# M_dulo_U_V_v_1_0.net
KiCad netlist of a schematic drawn in EAGLE
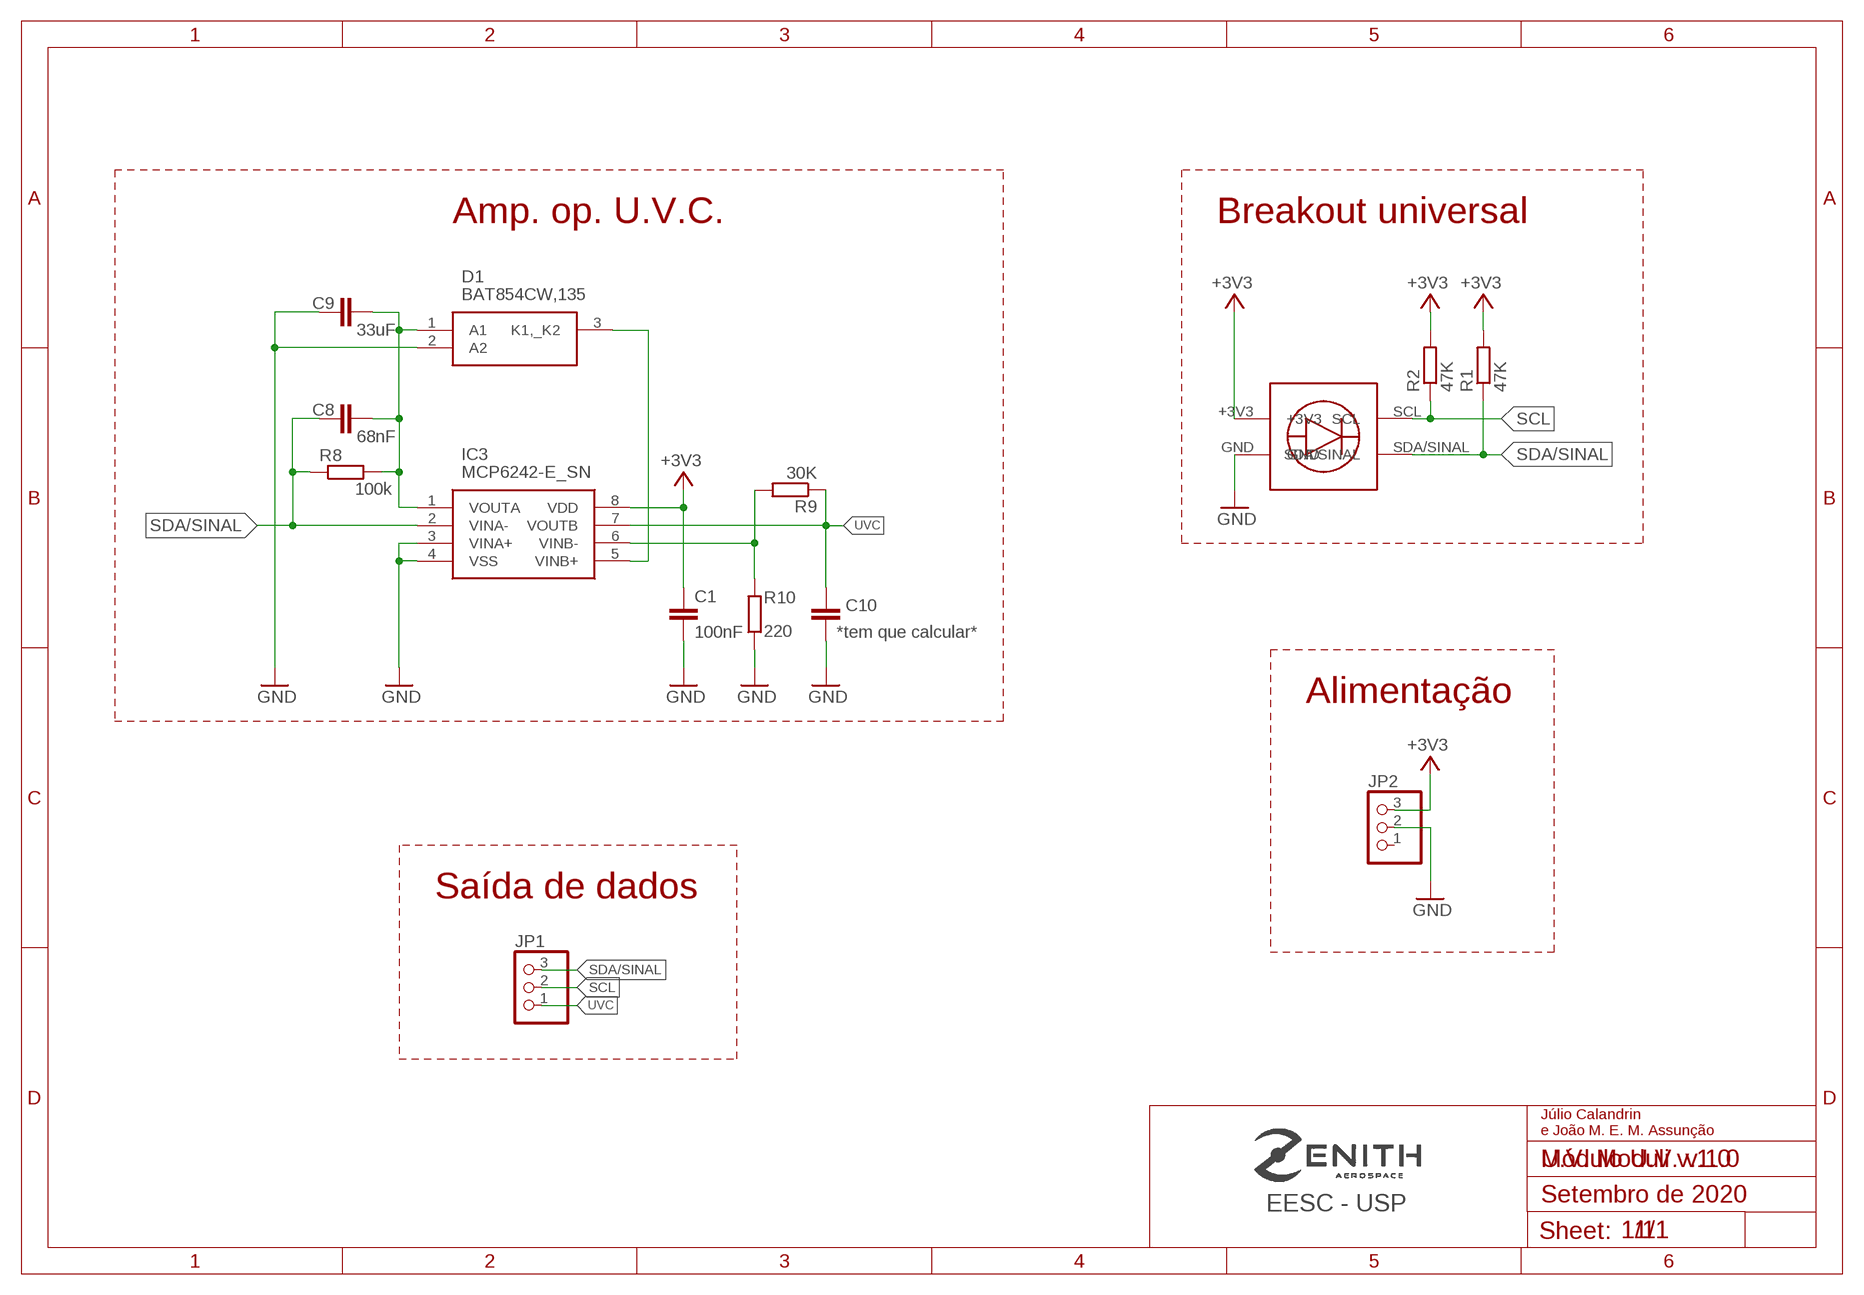
[diagram p0: schematic, sheet 1]

(export (version "E")
  (design (tool "Eeschema 10.0.6"))
  (components
    (comp (ref "C1")
      (value "100nF")
      (footprint "eagle-import:C0805")
      (libsource (lib "eagle-import") (part "C-EUC0805"))
    )
    (comp (ref "C8")
      (value "68nF")
      (footprint "eagle-import:C0805")
      (libsource (lib "eagle-import") (part "C-EUC0805"))
    )
    (comp (ref "C9")
      (value "33uF")
      (footprint "eagle-import:C0805")
      (libsource (lib "eagle-import") (part "C-EUC0805"))
    )
    (comp (ref "C10")
      (value "*tem que calcular*")
      (footprint "eagle-import:C0805")
      (libsource (lib "eagle-import") (part "C-EUC0805"))
    )
    (comp (ref "D1")
      (value "BAT854CW,135")
      (footprint "eagle-import:SOT65P210X110-3N")
      (fields (field (name "MOUSER_PART_NUMBER") "771-BAT854CW,135"))
      (libsource (lib "eagle-import") (part "BAT854CW,135"))
    )
    (comp (ref "IC3")
      (value "MCP6242-E_SN")
      (footprint "eagle-import:SOIC127P600X175-8N")
      (fields
        (field (name "MANUFACTURER_PART_NUMBER") "MCP6242-E/SN")
        (field (name "MOUSER_PART_NUMBER") "579-MCP6242-E/SN")
      )
      (libsource (lib "eagle-import") (part "MCP6242-E_SN"))
    )
    (comp (ref "JP1")
      (value "PINHD-1X3")
      (footprint "eagle-import:1X03")
      (libsource (lib "eagle-import") (part "PINHD-1X3"))
    )
    (comp (ref "JP2")
      (value "PINHD-1X3")
      (footprint "eagle-import:1X03")
      (libsource (lib "eagle-import") (part "PINHD-1X3"))
    )
    (comp (ref "R1")
      (value "47K")
      (footprint "eagle-import:R0805")
      (libsource (lib "eagle-import") (part "R-EU_R0805"))
    )
    (comp (ref "R2")
      (value "47K")
      (footprint "eagle-import:R0805")
      (libsource (lib "eagle-import") (part "R-EU_R0805"))
    )
    (comp (ref "R8")
      (value "100k")
      (footprint "eagle-import:R0805")
      (libsource (lib "eagle-import") (part "R-EU_R0805"))
    )
    (comp (ref "R9")
      (value "30K")
      (footprint "eagle-import:R0805")
      (libsource (lib "eagle-import") (part "R-EU_R0805"))
    )
    (comp (ref "R10")
      (value "220")
      (footprint "eagle-import:R0805")
      (libsource (lib "eagle-import") (part "R-EU_R0805"))
    )
    (comp (ref "U$1")
      (value "UNIVERSAL_BREAKOUT")
      (footprint "eagle-import:UNIVERSAL_PADS")
      (libsource (lib "eagle-import") (part "UNIVERSAL_BREAKOUT"))
    )
  )
  (nets
    (net (code "1") (name "+3V3") (class "Default")
      (node (ref "C1") (pin "1") (pinfunction "1_1") (pintype "passive"))
      (node (ref "IC3") (pin "8") (pinfunction "VDD_8") (pintype "bidirectional"))
      (node (ref "JP2") (pin "3") (pinfunction "3_3") (pintype "passive"))
      (node (ref "R1") (pin "2") (pinfunction "2_2") (pintype "passive"))
      (node (ref "R2") (pin "2") (pinfunction "2_2") (pintype "passive"))
      (node (ref "U$1") (pin "+3V3") (pinfunction "+3V3_+3V3") (pintype "bidirectional"))
    )
    (net (code "2") (name "GND") (class "Default")
      (node (ref "C1") (pin "2") (pinfunction "2_2") (pintype "passive"))
      (node (ref "C10") (pin "2") (pinfunction "2_2") (pintype "passive"))
      (node (ref "C9") (pin "2") (pinfunction "2_2") (pintype "passive"))
      (node (ref "D1") (pin "2") (pinfunction "A2_2") (pintype "input"))
      (node (ref "IC3") (pin "3") (pinfunction "VINA+_3") (pintype "bidirectional"))
      (node (ref "IC3") (pin "4") (pinfunction "VSS_4") (pintype "bidirectional"))
      (node (ref "JP2") (pin "2") (pinfunction "2_2") (pintype "passive"))
      (node (ref "R10") (pin "1") (pinfunction "1_1") (pintype "passive"))
      (node (ref "U$1") (pin "GND") (pinfunction "GND_GND") (pintype "bidirectional"))
    )
    (net (code "3") (name "Net-(D1-A1)") (class "Default")
      (node (ref "C8") (pin "2") (pinfunction "2_2") (pintype "passive"))
      (node (ref "C9") (pin "1") (pinfunction "1_1") (pintype "passive"))
      (node (ref "D1") (pin "1") (pinfunction "A1_1") (pintype "input"))
      (node (ref "IC3") (pin "1") (pinfunction "VOUTA_1") (pintype "bidirectional"))
      (node (ref "R8") (pin "2") (pinfunction "2_2") (pintype "passive"))
    )
    (net (code "4") (name "Net-(D1-K1,_K2)") (class "Default")
      (node (ref "D1") (pin "3") (pinfunction "K1,_K2_3") (pintype "output"))
      (node (ref "IC3") (pin "5") (pinfunction "VINB+_5") (pintype "bidirectional"))
    )
    (net (code "5") (name "Net-(IC3-VINB-)") (class "Default")
      (node (ref "IC3") (pin "6") (pinfunction "VINB-_6") (pintype "bidirectional"))
      (node (ref "R10") (pin "2") (pinfunction "2_2") (pintype "passive"))
      (node (ref "R9") (pin "2") (pinfunction "2_2") (pintype "passive"))
    )
    (net (code "6") (name "SCL") (class "Default")
      (node (ref "JP1") (pin "2") (pinfunction "2_2") (pintype "passive"))
      (node (ref "R2") (pin "1") (pinfunction "1_1") (pintype "passive"))
      (node (ref "U$1") (pin "SCL") (pinfunction "SCL_SCL") (pintype "bidirectional"))
    )
    (net (code "7") (name "SDA{slash}SINAL") (class "Default")
      (node (ref "C8") (pin "1") (pinfunction "1_1") (pintype "passive"))
      (node (ref "IC3") (pin "2") (pinfunction "VINA-_2") (pintype "bidirectional"))
      (node (ref "JP1") (pin "3") (pinfunction "3_3") (pintype "passive"))
      (node (ref "R1") (pin "1") (pinfunction "1_1") (pintype "passive"))
      (node (ref "R8") (pin "1") (pinfunction "1_1") (pintype "passive"))
      (node (ref "U$1") (pin "SDA/SINAL") (pinfunction "SDA/SINAL_SDA/SINAL") (pintype "bidirectional"))
    )
    (net (code "8") (name "UVC") (class "Default")
      (node (ref "C10") (pin "1") (pinfunction "1_1") (pintype "passive"))
      (node (ref "IC3") (pin "7") (pinfunction "VOUTB_7") (pintype "bidirectional"))
      (node (ref "JP1") (pin "1") (pinfunction "1_1") (pintype "passive"))
      (node (ref "R9") (pin "1") (pinfunction "1_1") (pintype "passive"))
    )
    (net (code "9") (name "unconnected-(JP2-Pad1)") (class "Default")
      (node (ref "JP2") (pin "1") (pinfunction "1_1") (pintype "passive"))
    )
  )
)
